# PyNab_Power.net
KiCad netlist of a schematic drawn in Altium Designer
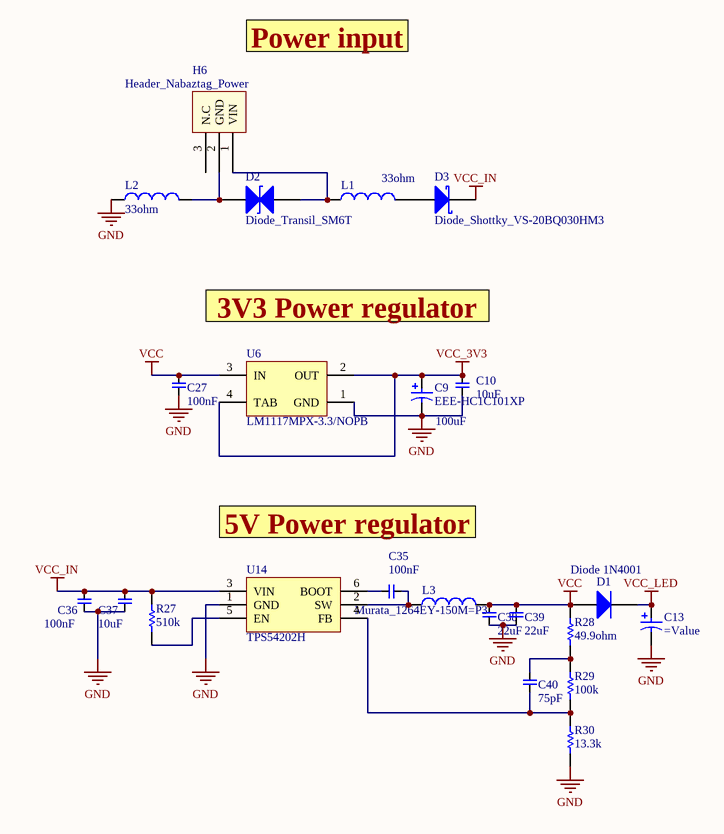
[diagram p0: PyNab_Power.SchDoc]

(export (version "E")
  (design (tool "Eeschema 10.0.6"))
  (components
    (comp (ref "C9")
      (value "EEE-HC1C101XP")
      (footprint "EEE-HC1C101XP")
      (fields (field (name "ALTIUM_VALUE") "100uF"))
      (libsource (lib "PassiveSMT") (part "VS0608 pol cap electro SMT"))
    )
    (comp (ref "C10")
      (value "10uF")
      (footprint "CAP0603")
      (description "Non-polarised capacitor")
      (libsource (lib "PassiveSMT") (part "Capacitor_np"))
    )
    (comp (ref "C13")
      (value "~")
      (footprint "CAPAE6083X105M")
      (description "Polarised capacitor")
      (libsource (lib "PassiveSMT") (part "Capacitor_pol"))
    )
    (comp (ref "C27")
      (value "100nF")
      (footprint "CAP0603")
      (description "Non-polarised capacitor")
      (libsource (lib "PassiveSMT") (part "Capacitor_np"))
    )
    (comp (ref "C35")
      (value "100nF")
      (footprint "CAP0603")
      (description "Non-polarised capacitor")
      (libsource (lib "PassiveSMT") (part "Capacitor_np"))
    )
    (comp (ref "C36")
      (value "100nF")
      (footprint "CAP0603")
      (description "Non-polarised capacitor")
      (libsource (lib "PassiveSMT") (part "Capacitor_np"))
    )
    (comp (ref "C37")
      (value "10uF")
      (footprint "CAP0603")
      (description "Non-polarised capacitor")
      (libsource (lib "PassiveSMT") (part "Capacitor_np"))
    )
    (comp (ref "C38")
      (value "22uF")
      (footprint "CAP0603")
      (description "Non-polarised capacitor")
      (libsource (lib "PassiveSMT") (part "Capacitor_np"))
    )
    (comp (ref "C39")
      (value "22uF")
      (footprint "CAP0603")
      (description "Non-polarised capacitor")
      (libsource (lib "PassiveSMT") (part "Capacitor_np"))
    )
    (comp (ref "C40")
      (value "75pF")
      (footprint "CAP0603")
      (description "Non-polarised capacitor")
      (libsource (lib "PassiveSMT") (part "Capacitor_np"))
    )
    (comp (ref "D1")
      (value "Diode 1N4001")
      (footprint "DO-41")
      (description "1 Amp General Purpose Rectifier")
      (fields (field (name "PUBLISHER") "Altium Limited"))
      (libsource (lib "Miscellaneous Devices") (part "Diode 1N4001"))
    )
    (comp (ref "D2")
      (value "Diode_Transil_SM6T")
      (footprint "Diode_Transil_SM6T")
      (libsource (lib "PassiveSMT") (part "Diode_Transil_SM6T"))
    )
    (comp (ref "D3")
      (value "Diode_Shottky_VS-20BQ030HM3")
      (footprint "Diode_Shottky_VS-20BQ030HM3")
      (libsource (lib "PassiveSMT") (part "Diode_Shottky_VS-20BQ030HM3"))
    )
    (comp (ref "H6")
      (value "Header_Nabaztag_Power")
      (footprint "HDR3x1_Nabaztag_pwr")
      (description "Power Header")
      (libsource (lib "Enero_HEADERS") (part "Header_Nabaztag_Power"))
    )
    (comp (ref "L1")
      (value "33ohm")
      (footprint "IND0603")
      (description "Inductor 0603 blm18pg330sn")
      (libsource (lib "PassiveSMT") (part "Inductor1"))
    )
    (comp (ref "L2")
      (value "33ohm")
      (footprint "IND0603")
      (description "Inductor 0603 blm18pg330sn")
      (libsource (lib "PassiveSMT") (part "Inductor1"))
    )
    (comp (ref "L3")
      (value "Murata_1264EY-150M=P3")
      (footprint "Murata-1264EY-150M=P3")
      (description "Inductor")
      (libsource (lib "") (part "Inductor1_1"))
    )
    (comp (ref "R27")
      (value "510k")
      (footprint "RES0603")
      (description "Resistor")
      (libsource (lib "PassiveSMT") (part "Resistor1"))
    )
    (comp (ref "R28")
      (value "49.9ohm")
      (footprint "RES0603")
      (description "Resistor")
      (libsource (lib "PassiveSMT") (part "Resistor1"))
    )
    (comp (ref "R29")
      (value "100k")
      (footprint "RES0603")
      (description "Resistor")
      (libsource (lib "PassiveSMT") (part "Resistor1"))
    )
    (comp (ref "R30")
      (value "13.3k")
      (footprint "RES0603")
      (description "Resistor")
      (libsource (lib "PassiveSMT") (part "Resistor1"))
    )
    (comp (ref "U6")
      (value "LM1117MPX-3.3/NOPB")
      (footprint "MP04A_N")
      (description "800mA Low-Dropout Linear Regulator, 4-pin SOT-223, Pb-Free")
      (fields (field (name "MANUFACTURER") "National Semiconductor"))
      (libsource (lib "National Semiconductor LDO") (part "LM1117MPX-3.3/NOPB"))
    )
    (comp (ref "U14")
      (value "TPS54202H")
      (footprint "SOT95P280X110-6N")
      (libsource (lib "TPS54202H") (part "TPS54202H"))
    )
  )
  (nets
    (net (code "1") (name "GND") (class "Default")
      (node (ref "C10") (pin "1") (pinfunction "1_1") (pintype "passive"))
      (node (ref "C13") (pin "2") (pinfunction "K_2") (pintype "passive"))
      (node (ref "C27") (pin "1") (pinfunction "1_1") (pintype "passive"))
      (node (ref "C36") (pin "1") (pinfunction "1_1") (pintype "passive"))
      (node (ref "C37") (pin "1") (pinfunction "1_1") (pintype "passive"))
      (node (ref "C38") (pin "1") (pinfunction "1_1") (pintype "passive"))
      (node (ref "C39") (pin "1") (pinfunction "1_1") (pintype "passive"))
      (node (ref "C9") (pin "1") (pinfunction "K_1") (pintype "passive"))
      (node (ref "L2") (pin "2") (pinfunction "2_2") (pintype "passive"))
      (node (ref "R30") (pin "1") (pinfunction "1_1") (pintype "passive"))
      (node (ref "U14") (pin "1") (pinfunction "GND_1") (pintype "passive"))
      (node (ref "U6") (pin "1") (pinfunction "GND_1") (pintype "power_in"))
    )
    (net (code "2") (name "Net-(C40-Pad1)") (class "Default")
      (node (ref "C40") (pin "1") (pinfunction "1_1") (pintype "passive"))
      (node (ref "R28") (pin "1") (pinfunction "1_1") (pintype "passive"))
      (node (ref "R29") (pin "2") (pinfunction "2_2") (pintype "passive"))
    )
    (net (code "3") (name "Net-(D3-A)") (class "Default")
      (node (ref "D3") (pin "2") (pinfunction "A_2") (pintype "passive"))
      (node (ref "L1") (pin "1") (pinfunction "1_1") (pintype "passive"))
    )
    (net (code "4") (name "Net-(H6-GND)") (class "Default")
      (node (ref "D2") (pin "1") (pintype "passive"))
      (node (ref "H6") (pin "2") (pinfunction "GND_2") (pintype "passive"))
      (node (ref "L2") (pin "1") (pinfunction "1_1") (pintype "passive"))
    )
    (net (code "5") (name "Net-(H6-VIN)") (class "Default")
      (node (ref "D2") (pin "2") (pintype "passive"))
      (node (ref "H6") (pin "1") (pinfunction "VIN_1") (pintype "passive"))
      (node (ref "L1") (pin "2") (pinfunction "2_2") (pintype "passive"))
    )
    (net (code "6") (name "Net-(U14-BOOT)") (class "Default")
      (node (ref "C35") (pin "2") (pinfunction "2_2") (pintype "passive"))
      (node (ref "U14") (pin "6") (pinfunction "BOOT_6") (pintype "passive"))
    )
    (net (code "7") (name "Net-(U14-EN)") (class "Default")
      (node (ref "R27") (pin "2") (pinfunction "2_2") (pintype "passive"))
      (node (ref "U14") (pin "5") (pinfunction "EN_5") (pintype "passive"))
    )
    (net (code "8") (name "Net-(U14-FB)") (class "Default")
      (node (ref "C40") (pin "2") (pinfunction "2_2") (pintype "passive"))
      (node (ref "R29") (pin "1") (pinfunction "1_1") (pintype "passive"))
      (node (ref "R30") (pin "2") (pinfunction "2_2") (pintype "passive"))
      (node (ref "U14") (pin "4") (pinfunction "FB_4") (pintype "passive"))
    )
    (net (code "9") (name "Net-(U14-SW)") (class "Default")
      (node (ref "C35") (pin "1") (pinfunction "1_1") (pintype "passive"))
      (node (ref "L3") (pin "1") (pinfunction "1_1") (pintype "passive"))
      (node (ref "U14") (pin "2") (pinfunction "SW_2") (pintype "passive"))
    )
    (net (code "10") (name "VCC") (class "Default")
      (node (ref "C27") (pin "2") (pinfunction "2_2") (pintype "passive"))
      (node (ref "C38") (pin "2") (pinfunction "2_2") (pintype "passive"))
      (node (ref "C39") (pin "2") (pinfunction "2_2") (pintype "passive"))
      (node (ref "D1") (pin "1") (pinfunction "A_1") (pintype "passive"))
      (node (ref "L3") (pin "2") (pinfunction "2_2") (pintype "passive"))
      (node (ref "R28") (pin "2") (pinfunction "2_2") (pintype "passive"))
      (node (ref "U6") (pin "3") (pinfunction "IN_3") (pintype "power_in"))
    )
    (net (code "11") (name "VCC_3V3") (class "Default")
      (node (ref "C10") (pin "2") (pinfunction "2_2") (pintype "passive"))
      (node (ref "C9") (pin "2") (pinfunction "A_2") (pintype "passive"))
      (node (ref "U6") (pin "2") (pinfunction "OUT_2") (pintype "power_in"))
      (node (ref "U6") (pin "4") (pinfunction "TAB_4") (pintype "power_in"))
    )
    (net (code "12") (name "VCC_IN") (class "Default")
      (node (ref "C36") (pin "2") (pinfunction "2_2") (pintype "passive"))
      (node (ref "C37") (pin "2") (pinfunction "2_2") (pintype "passive"))
      (node (ref "D3") (pin "1") (pinfunction "K_1") (pintype "passive"))
      (node (ref "R27") (pin "1") (pinfunction "1_1") (pintype "passive"))
      (node (ref "U14") (pin "3") (pinfunction "VIN_3") (pintype "passive"))
    )
    (net (code "13") (name "VCC_LED") (class "Default")
      (node (ref "C13") (pin "1") (pinfunction "A_1") (pintype "passive"))
      (node (ref "D1") (pin "2") (pinfunction "K_2") (pintype "passive"))
    )
    (net (code "14") (name "unconnected-(H6-N.C-Pad3)") (class "Default")
      (node (ref "H6") (pin "3") (pinfunction "N.C_3") (pintype "passive"))
    )
  )
)
